# uNav4x4r1.net
KiCad netlist of a schematic drawn in EAGLE
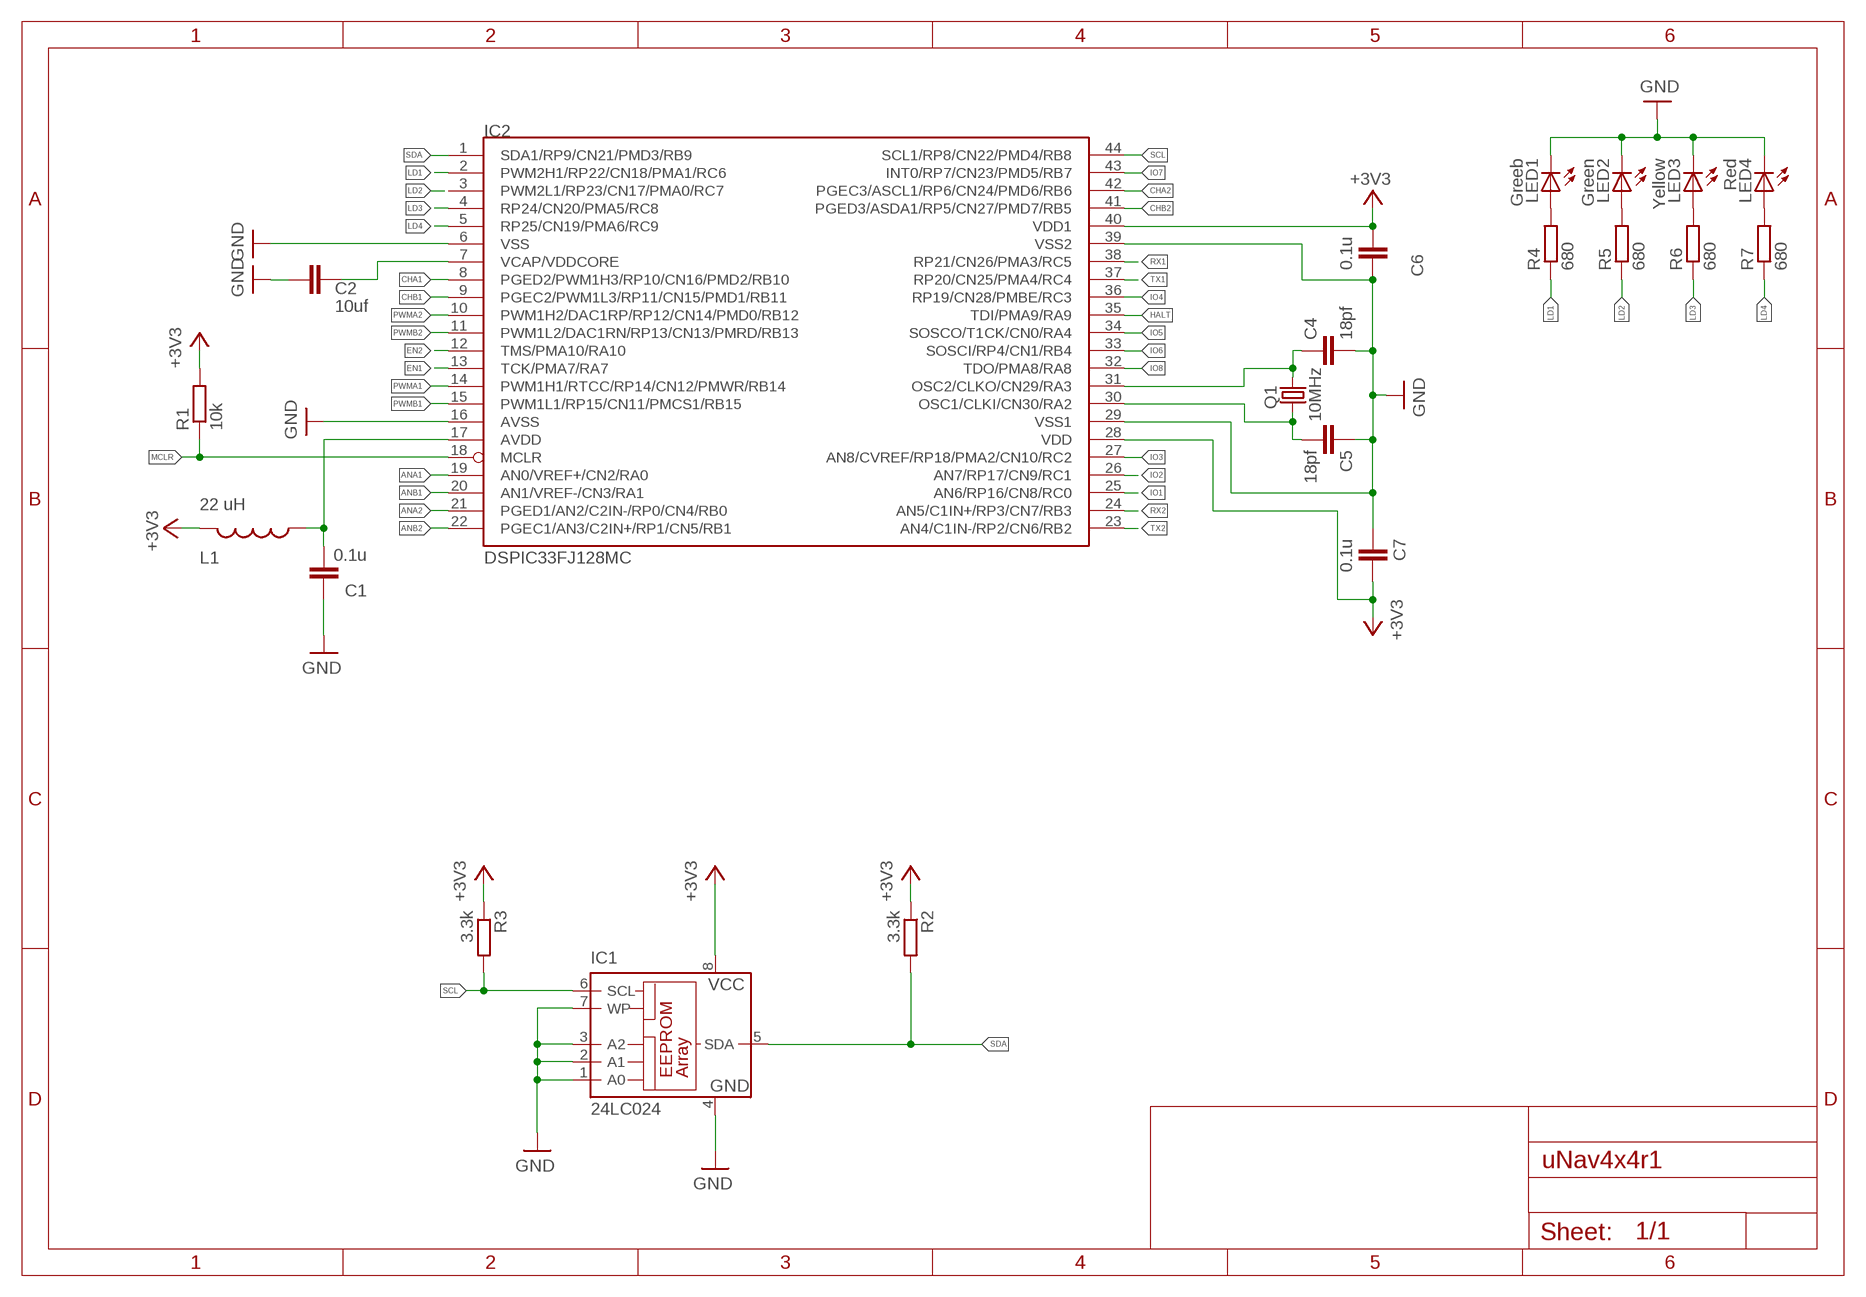
[diagram p0: schematic, sheet 1, part 1 of 2]
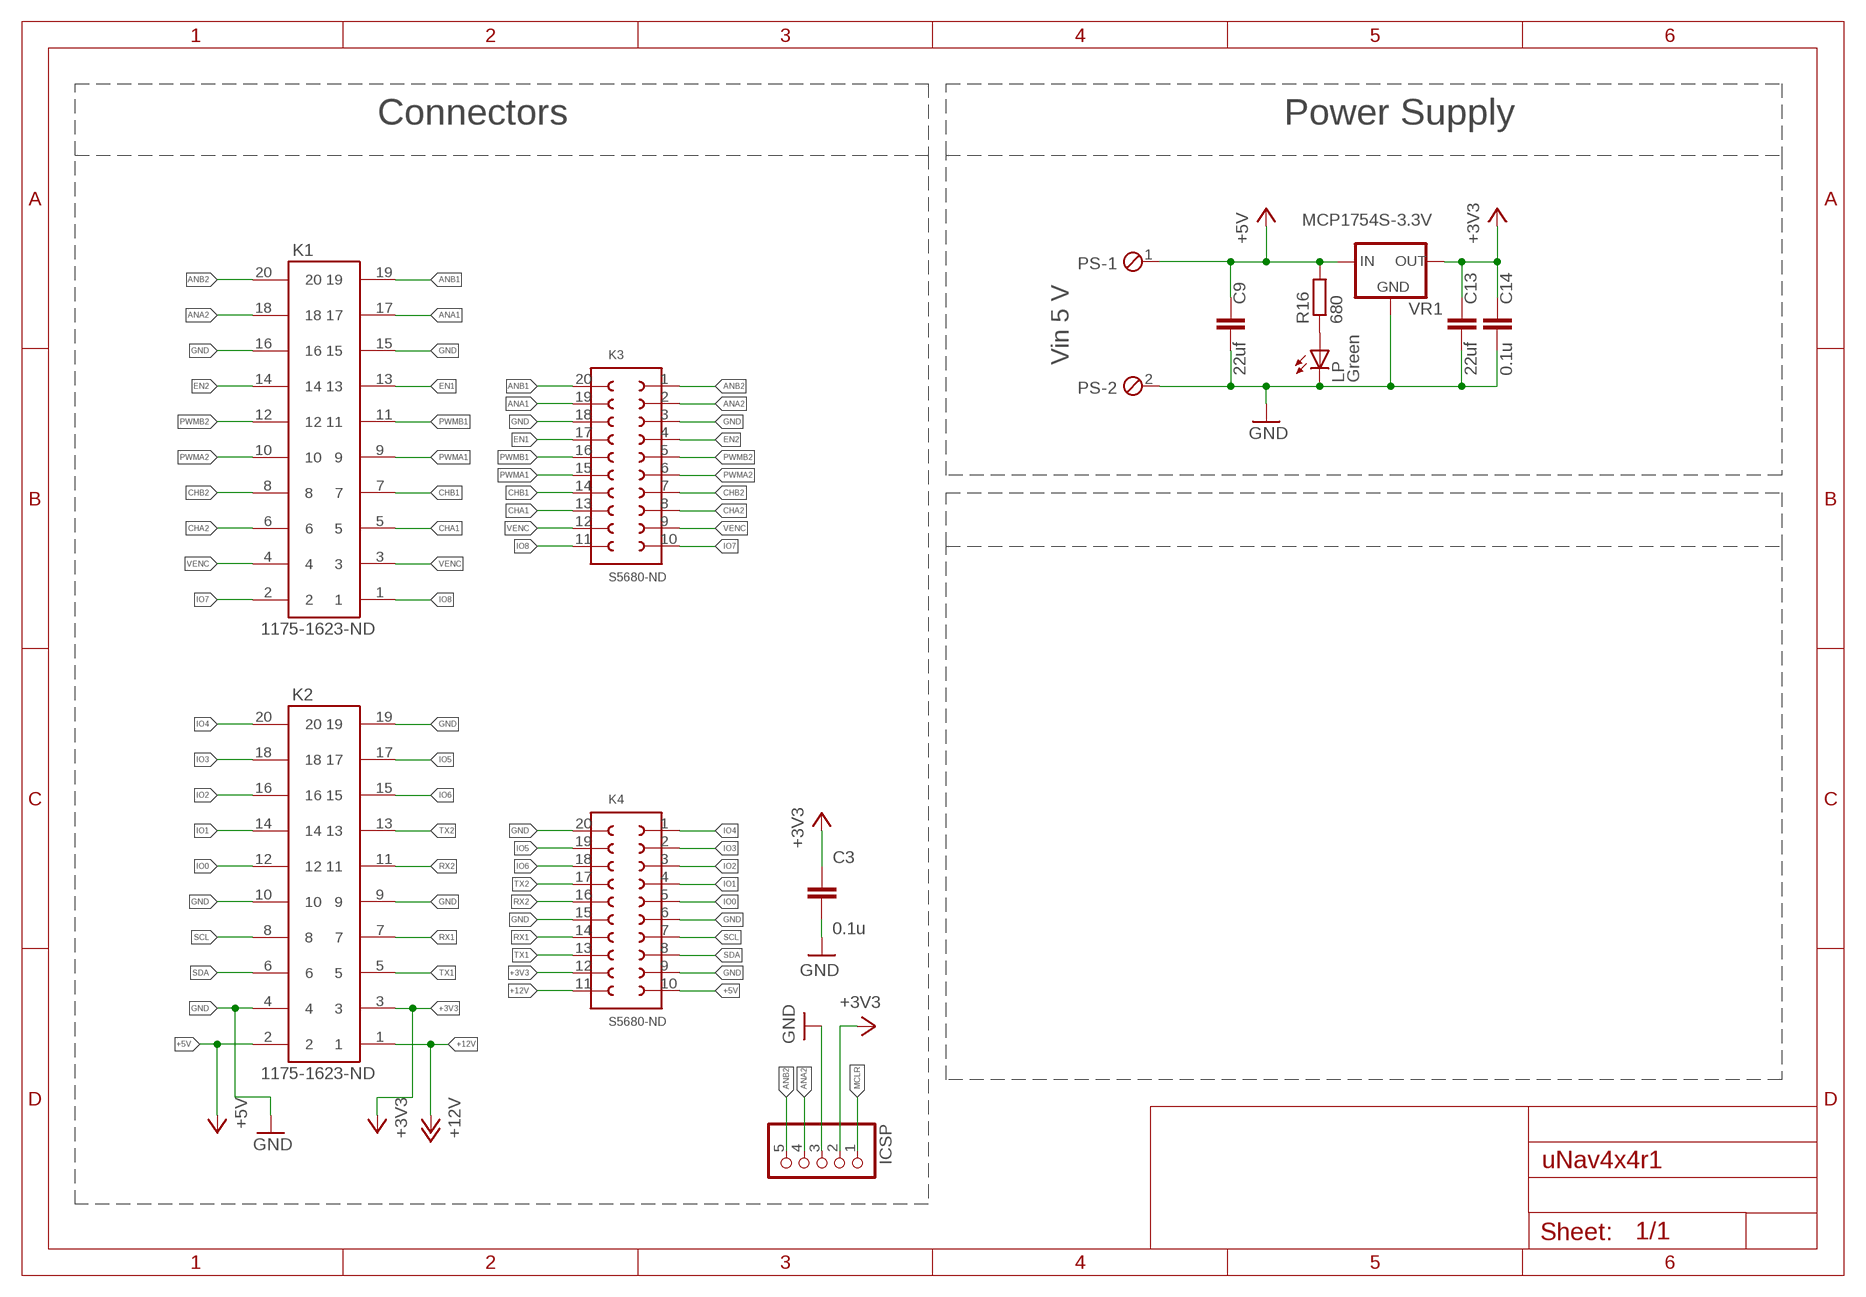
[diagram p1: schematic, sheet 1, part 2 of 2]

(export (version "E")
  (design (tool "Eeschema 10.0.6"))
  (components
    (comp (ref "C1")
      (value "0.1u")
      (footprint "eagle-import:C0603")
      (libsource (lib "eagle-import") (part "C-EUC0603"))
    )
    (comp (ref "C2")
      (value "10uf")
      (footprint "eagle-import:C1206")
      (libsource (lib "eagle-import") (part "C-EUC1206"))
    )
    (comp (ref "C3")
      (value "0.1u")
      (footprint "eagle-import:C0603")
      (libsource (lib "eagle-import") (part "C-EUC0603"))
    )
    (comp (ref "C4")
      (value "18pf")
      (footprint "eagle-import:C0603")
      (libsource (lib "eagle-import") (part "C-EUC0603"))
    )
    (comp (ref "C5")
      (value "18pf")
      (footprint "eagle-import:C0603")
      (libsource (lib "eagle-import") (part "C-EUC0603"))
    )
    (comp (ref "C6")
      (value "0.1u")
      (footprint "eagle-import:C0603")
      (libsource (lib "eagle-import") (part "C-EUC0603"))
    )
    (comp (ref "C7")
      (value "0.1u")
      (footprint "eagle-import:C0603")
      (libsource (lib "eagle-import") (part "C-EUC0603"))
    )
    (comp (ref "C9")
      (value "22uf")
      (footprint "eagle-import:C1206")
      (libsource (lib "eagle-import") (part "C-EUC1206"))
    )
    (comp (ref "C13")
      (value "22uf")
      (footprint "eagle-import:C1206")
      (libsource (lib "eagle-import") (part "C-EUC1206"))
    )
    (comp (ref "C14")
      (value "0.1u")
      (footprint "eagle-import:C0603")
      (libsource (lib "eagle-import") (part "C-EUC0603"))
    )
    (comp (ref "IC1")
      (value "24LC024")
      (footprint "eagle-import:SO-08M")
      (fields (field (name "MF") "MICROCHIP") (field (name "MPN") "24AA01-I/SN"))
      (libsource (lib "eagle-import") (part "24SMAA01"))
    )
    (comp (ref "IC2")
      (value "DSPIC33FJ128MC")
      (footprint "eagle-import:TQFP44")
      (libsource (lib "eagle-import") (part "DSPIC33FJ128MC804-PT"))
    )
    (comp (ref "ICSP")
      (value "PINHD-1X05_2.54-S")
      (footprint "eagle-import:1X05-S")
      (libsource (lib "eagle-import") (part "PINHD-1X05_2.54-S"))
    )
    (comp (ref "K1")
      (value "1175-1623-ND")
      (footprint "eagle-import:612X2020621")
      (libsource (lib "eagle-import") (part "612X2020621"))
    )
    (comp (ref "K2")
      (value "1175-1623-ND")
      (footprint "eagle-import:612X2020621")
      (libsource (lib "eagle-import") (part "612X2020621"))
    )
    (comp (ref "K3")
      (value "S5680-ND")
      (footprint "eagle-import:61002021821")
      (libsource (lib "eagle-import") (part "61002021821"))
    )
    (comp (ref "K4")
      (value "S5680-ND")
      (footprint "eagle-import:61002021821")
      (libsource (lib "eagle-import") (part "61002021821"))
    )
    (comp (ref "L1")
      (value "22 uH")
      (footprint "eagle-import:0805")
      (libsource (lib "eagle-import") (part "INDUCTOR0805"))
    )
    (comp (ref "LED1")
      (value "Greeb")
      (footprint "eagle-import:CHIPLED_0805")
      (libsource (lib "eagle-import") (part "LEDCHIPLED_0805"))
    )
    (comp (ref "LED2")
      (value "Green")
      (footprint "eagle-import:CHIPLED_0805")
      (libsource (lib "eagle-import") (part "LEDCHIPLED_0805"))
    )
    (comp (ref "LED3")
      (value "Yellow")
      (footprint "eagle-import:CHIPLED_0805")
      (libsource (lib "eagle-import") (part "LEDCHIPLED_0805"))
    )
    (comp (ref "LED4")
      (value "Red")
      (footprint "eagle-import:CHIPLED_0805")
      (libsource (lib "eagle-import") (part "LEDCHIPLED_0805"))
    )
    (comp (ref "LP")
      (value "Green")
      (footprint "eagle-import:CHIPLED_0805")
      (libsource (lib "eagle-import") (part "LEDCHIPLED_0805"))
    )
    (comp (ref "PS")
      (value "MPT2")
      (footprint "eagle-import:2POL254")
      (libsource (lib "eagle-import") (part "MPT2"))
    )
    (comp (ref "Q1")
      (value "10MHz")
      (footprint "eagle-import:HC49U-V")
      (libsource (lib "eagle-import") (part "CRYSTALHC49U-V"))
    )
    (comp (ref "R1")
      (value "10k")
      (footprint "eagle-import:R0603")
      (libsource (lib "eagle-import") (part "R-EU_R0603"))
    )
    (comp (ref "R2")
      (value "3.3k")
      (footprint "eagle-import:R0603")
      (libsource (lib "eagle-import") (part "R-EU_R0603"))
    )
    (comp (ref "R3")
      (value "3.3k")
      (footprint "eagle-import:R0603")
      (libsource (lib "eagle-import") (part "R-EU_R0603"))
    )
    (comp (ref "R4")
      (value "680")
      (footprint "eagle-import:R0603")
      (libsource (lib "eagle-import") (part "R-EU_R0603"))
    )
    (comp (ref "R5")
      (value "680")
      (footprint "eagle-import:R0603")
      (libsource (lib "eagle-import") (part "R-EU_R0603"))
    )
    (comp (ref "R6")
      (value "680")
      (footprint "eagle-import:R0603")
      (libsource (lib "eagle-import") (part "R-EU_R0603"))
    )
    (comp (ref "R7")
      (value "680")
      (footprint "eagle-import:R0603")
      (libsource (lib "eagle-import") (part "R-EU_R0603"))
    )
    (comp (ref "R16")
      (value "680")
      (footprint "eagle-import:R0603")
      (libsource (lib "eagle-import") (part "R-EU_R0603"))
    )
    (comp (ref "VR1")
      (value "MCP1754S-3.3V")
      (footprint "eagle-import:SOT89")
      (libsource (lib "eagle-import") (part "MCP1754S"))
    )
  )
  (nets
    (net (code "1") (name "+3V3") (class "Default")
      (node (ref "C13") (pin "1") (pinfunction "1_1") (pintype "passive"))
      (node (ref "C14") (pin "1") (pinfunction "1_1") (pintype "passive"))
      (node (ref "C3") (pin "1") (pinfunction "1_1") (pintype "passive"))
      (node (ref "C6") (pin "2") (pinfunction "2_2") (pintype "passive"))
      (node (ref "C7") (pin "1") (pinfunction "1_1") (pintype "passive"))
      (node (ref "IC1") (pin "8") (pinfunction "VCC_8") (pintype "power_in"))
      (node (ref "IC2") (pin "28") (pinfunction "VDD_28") (pintype "power_in"))
      (node (ref "IC2") (pin "40") (pinfunction "VDD1_40") (pintype "power_in"))
      (node (ref "ICSP") (pin "2") (pinfunction "2_2") (pintype "passive"))
      (node (ref "K2") (pin "3") (pinfunction "3_3") (pintype "passive"))
      (node (ref "K4") (pin "12") (pinfunction "12_12") (pintype "passive"))
      (node (ref "L1") (pin "2") (pinfunction "2_2") (pintype "passive"))
      (node (ref "R1") (pin "2") (pinfunction "2_2") (pintype "passive"))
      (node (ref "R2") (pin "1") (pinfunction "1_1") (pintype "passive"))
      (node (ref "R3") (pin "1") (pinfunction "1_1") (pintype "passive"))
      (node (ref "VR1") (pin "3") (pinfunction "OUT_3") (pintype "passive"))
    )
    (net (code "2") (name "+5V") (class "Default")
      (node (ref "C9") (pin "1") (pinfunction "1_1") (pintype "passive"))
      (node (ref "K2") (pin "2") (pinfunction "2_2") (pintype "passive"))
      (node (ref "K4") (pin "10") (pinfunction "10_10") (pintype "passive"))
      (node (ref "PS") (pin "1") (pinfunction "1_1") (pintype "passive"))
      (node (ref "R16") (pin "2") (pinfunction "2_2") (pintype "passive"))
      (node (ref "VR1") (pin "1") (pinfunction "IN_1") (pintype "input"))
    )
    (net (code "3") (name "+12V") (class "Default")
      (node (ref "K2") (pin "1") (pinfunction "1_1") (pintype "passive"))
      (node (ref "K4") (pin "11") (pinfunction "11_11") (pintype "passive"))
    )
    (net (code "4") (name "ANA1") (class "Default")
      (node (ref "IC2") (pin "19") (pinfunction "AN0/VREF+/CN2/RA0_19") (pintype "bidirectional"))
      (node (ref "K1") (pin "17") (pinfunction "17_17") (pintype "passive"))
      (node (ref "K3") (pin "19") (pinfunction "19_19") (pintype "passive"))
    )
    (net (code "5") (name "ANA2") (class "Default")
      (node (ref "IC2") (pin "21") (pinfunction "PGED1/AN2/C2IN-/RP0/CN4/RB0_21") (pintype "bidirectional"))
      (node (ref "ICSP") (pin "4") (pinfunction "4_4") (pintype "passive"))
      (node (ref "K1") (pin "18") (pinfunction "18_18") (pintype "passive"))
      (node (ref "K3") (pin "2") (pinfunction "2_2") (pintype "passive"))
    )
    (net (code "6") (name "ANB1") (class "Default")
      (node (ref "IC2") (pin "20") (pinfunction "AN1/VREF-/CN3/RA1_20") (pintype "bidirectional"))
      (node (ref "K1") (pin "19") (pinfunction "19_19") (pintype "passive"))
      (node (ref "K3") (pin "20") (pinfunction "20_20") (pintype "passive"))
    )
    (net (code "7") (name "ANB2") (class "Default")
      (node (ref "IC2") (pin "22") (pinfunction "PGEC1/AN3/C2IN+/RP1/CN5/RB1_22") (pintype "bidirectional"))
      (node (ref "ICSP") (pin "5") (pinfunction "5_5") (pintype "passive"))
      (node (ref "K1") (pin "20") (pinfunction "20_20") (pintype "passive"))
      (node (ref "K3") (pin "1") (pinfunction "1_1") (pintype "passive"))
    )
    (net (code "8") (name "CHA1") (class "Default")
      (node (ref "IC2") (pin "8") (pinfunction "PGED2/PWM1H3/RP10/CN16/PMD2/RB10_8") (pintype "bidirectional"))
      (node (ref "K1") (pin "5") (pinfunction "5_5") (pintype "passive"))
      (node (ref "K3") (pin "13") (pinfunction "13_13") (pintype "passive"))
    )
    (net (code "9") (name "CHA2") (class "Default")
      (node (ref "IC2") (pin "42") (pinfunction "PGEC3/ASCL1/RP6/CN24/PMD6/RB6_42") (pintype "bidirectional"))
      (node (ref "K1") (pin "6") (pinfunction "6_6") (pintype "passive"))
      (node (ref "K3") (pin "8") (pinfunction "8_8") (pintype "passive"))
    )
    (net (code "10") (name "CHB1") (class "Default")
      (node (ref "IC2") (pin "9") (pinfunction "PGEC2/PWM1L3/RP11/CN15/PMD1/RB11_9") (pintype "bidirectional"))
      (node (ref "K1") (pin "7") (pinfunction "7_7") (pintype "passive"))
      (node (ref "K3") (pin "14") (pinfunction "14_14") (pintype "passive"))
    )
    (net (code "11") (name "CHB2") (class "Default")
      (node (ref "IC2") (pin "41") (pinfunction "PGED3/ASDA1/RP5/CN27/PMD7/RB5_41") (pintype "bidirectional"))
      (node (ref "K1") (pin "8") (pinfunction "8_8") (pintype "passive"))
      (node (ref "K3") (pin "7") (pinfunction "7_7") (pintype "passive"))
    )
    (net (code "12") (name "EN1") (class "Default")
      (node (ref "IC2") (pin "13") (pinfunction "TCK/PMA7/RA7_13") (pintype "bidirectional"))
      (node (ref "K1") (pin "13") (pinfunction "13_13") (pintype "passive"))
      (node (ref "K3") (pin "17") (pinfunction "17_17") (pintype "passive"))
    )
    (net (code "13") (name "EN2") (class "Default")
      (node (ref "IC2") (pin "12") (pinfunction "TMS/PMA10/RA10_12") (pintype "bidirectional"))
      (node (ref "K1") (pin "14") (pinfunction "14_14") (pintype "passive"))
      (node (ref "K3") (pin "4") (pinfunction "4_4") (pintype "passive"))
    )
    (net (code "14") (name "GND") (class "Default")
      (node (ref "C1") (pin "1") (pinfunction "1_1") (pintype "passive"))
      (node (ref "C13") (pin "2") (pinfunction "2_2") (pintype "passive"))
      (node (ref "C14") (pin "2") (pinfunction "2_2") (pintype "passive"))
      (node (ref "C2") (pin "2") (pinfunction "2_2") (pintype "passive"))
      (node (ref "C3") (pin "2") (pinfunction "2_2") (pintype "passive"))
      (node (ref "C4") (pin "2") (pinfunction "2_2") (pintype "passive"))
      (node (ref "C5") (pin "1") (pinfunction "1_1") (pintype "passive"))
      (node (ref "C6") (pin "1") (pinfunction "1_1") (pintype "passive"))
      (node (ref "C7") (pin "2") (pinfunction "2_2") (pintype "passive"))
      (node (ref "C9") (pin "2") (pinfunction "2_2") (pintype "passive"))
      (node (ref "IC1") (pin "1") (pinfunction "A0_1") (pintype "input"))
      (node (ref "IC1") (pin "2") (pinfunction "A1_2") (pintype "input"))
      (node (ref "IC1") (pin "3") (pinfunction "A2_3") (pintype "input"))
      (node (ref "IC1") (pin "4") (pinfunction "GND_4") (pintype "power_in"))
      (node (ref "IC1") (pin "7") (pinfunction "WP_7") (pintype "input"))
      (node (ref "IC2") (pin "16") (pinfunction "AVSS_16") (pintype "power_in"))
      (node (ref "IC2") (pin "29") (pinfunction "VSS1_29") (pintype "power_in"))
      (node (ref "IC2") (pin "39") (pinfunction "VSS2_39") (pintype "power_in"))
      (node (ref "IC2") (pin "6") (pinfunction "VSS_6") (pintype "power_in"))
      (node (ref "ICSP") (pin "3") (pinfunction "3_3") (pintype "passive"))
      (node (ref "K1") (pin "15") (pinfunction "15_15") (pintype "passive"))
      (node (ref "K1") (pin "16") (pinfunction "16_16") (pintype "passive"))
      (node (ref "K2") (pin "10") (pinfunction "10_10") (pintype "passive"))
      (node (ref "K2") (pin "19") (pinfunction "19_19") (pintype "passive"))
      (node (ref "K2") (pin "4") (pinfunction "4_4") (pintype "passive"))
      (node (ref "K2") (pin "9") (pinfunction "9_9") (pintype "passive"))
      (node (ref "K3") (pin "18") (pinfunction "18_18") (pintype "passive"))
      (node (ref "K3") (pin "3") (pinfunction "3_3") (pintype "passive"))
      (node (ref "K4") (pin "15") (pinfunction "15_15") (pintype "passive"))
      (node (ref "K4") (pin "20") (pinfunction "20_20") (pintype "passive"))
      (node (ref "K4") (pin "6") (pinfunction "6_6") (pintype "passive"))
      (node (ref "K4") (pin "9") (pinfunction "9_9") (pintype "passive"))
      (node (ref "LED1") (pin "C") (pinfunction "C_C") (pintype "passive"))
      (node (ref "LED2") (pin "C") (pinfunction "C_C") (pintype "passive"))
      (node (ref "LED3") (pin "C") (pinfunction "C_C") (pintype "passive"))
      (node (ref "LED4") (pin "C") (pinfunction "C_C") (pintype "passive"))
      (node (ref "LP") (pin "C") (pinfunction "C_C") (pintype "passive"))
      (node (ref "PS") (pin "2") (pinfunction "1_2") (pintype "passive"))
      (node (ref "VR1") (pin "2") (pinfunction "GND_2") (pintype "input"))
      (node (ref "VR1") (pin "4") (pinfunction "GND_4") (pintype "input"))
    )
    (net (code "15") (name "HALT") (class "Default")
      (node (ref "IC2") (pin "35") (pinfunction "TDI/PMA9/RA9_35") (pintype "bidirectional"))
    )
    (net (code "16") (name "IO0") (class "Default")
      (node (ref "K2") (pin "12") (pinfunction "12_12") (pintype "passive"))
      (node (ref "K4") (pin "5") (pinfunction "5_5") (pintype "passive"))
    )
    (net (code "17") (name "IO1") (class "Default")
      (node (ref "IC2") (pin "25") (pinfunction "AN6/RP16/CN8/RC0_25") (pintype "bidirectional"))
      (node (ref "K2") (pin "14") (pinfunction "14_14") (pintype "passive"))
      (node (ref "K4") (pin "4") (pinfunction "4_4") (pintype "passive"))
    )
    (net (code "18") (name "IO2") (class "Default")
      (node (ref "IC2") (pin "26") (pinfunction "AN7/RP17/CN9/RC1_26") (pintype "bidirectional"))
      (node (ref "K2") (pin "16") (pinfunction "16_16") (pintype "passive"))
      (node (ref "K4") (pin "3") (pinfunction "3_3") (pintype "passive"))
    )
    (net (code "19") (name "IO3") (class "Default")
      (node (ref "IC2") (pin "27") (pinfunction "AN8/CVREF/RP18/PMA2/CN10/RC2_27") (pintype "bidirectional"))
      (node (ref "K2") (pin "18") (pinfunction "18_18") (pintype "passive"))
      (node (ref "K4") (pin "2") (pinfunction "2_2") (pintype "passive"))
    )
    (net (code "20") (name "IO4") (class "Default")
      (node (ref "IC2") (pin "36") (pinfunction "RP19/CN28/PMBE/RC3_36") (pintype "bidirectional"))
      (node (ref "K2") (pin "20") (pinfunction "20_20") (pintype "passive"))
      (node (ref "K4") (pin "1") (pinfunction "1_1") (pintype "passive"))
    )
    (net (code "21") (name "IO5") (class "Default")
      (node (ref "IC2") (pin "34") (pinfunction "SOSCO/T1CK/CN0/RA4_34") (pintype "bidirectional"))
      (node (ref "K2") (pin "17") (pinfunction "17_17") (pintype "passive"))
      (node (ref "K4") (pin "19") (pinfunction "19_19") (pintype "passive"))
    )
    (net (code "22") (name "IO6") (class "Default")
      (node (ref "IC2") (pin "33") (pinfunction "SOSCI/RP4/CN1/RB4_33") (pintype "bidirectional"))
      (node (ref "K2") (pin "15") (pinfunction "15_15") (pintype "passive"))
      (node (ref "K4") (pin "18") (pinfunction "18_18") (pintype "passive"))
    )
    (net (code "23") (name "IO7") (class "Default")
      (node (ref "IC2") (pin "43") (pinfunction "INT0/RP7/CN23/PMD5/RB7_43") (pintype "bidirectional"))
      (node (ref "K1") (pin "2") (pinfunction "2_2") (pintype "passive"))
      (node (ref "K3") (pin "10") (pinfunction "10_10") (pintype "passive"))
    )
    (net (code "24") (name "IO8") (class "Default")
      (node (ref "IC2") (pin "32") (pinfunction "TDO/PMA8/RA8_32") (pintype "bidirectional"))
      (node (ref "K1") (pin "1") (pinfunction "1_1") (pintype "passive"))
      (node (ref "K3") (pin "11") (pinfunction "11_11") (pintype "passive"))
    )
    (net (code "25") (name "LD1") (class "Default")
      (node (ref "IC2") (pin "2") (pinfunction "PWM2H1/RP22/CN18/PMA1/RC6_2") (pintype "bidirectional"))
      (node (ref "R4") (pin "1") (pinfunction "1_1") (pintype "passive"))
    )
    (net (code "26") (name "LD2") (class "Default")
      (node (ref "IC2") (pin "3") (pinfunction "PWM2L1/RP23/CN17/PMA0/RC7_3") (pintype "bidirectional"))
      (node (ref "R5") (pin "1") (pinfunction "1_1") (pintype "passive"))
    )
    (net (code "27") (name "LD3") (class "Default")
      (node (ref "IC2") (pin "4") (pinfunction "RP24/CN20/PMA5/RC8_4") (pintype "bidirectional"))
      (node (ref "R6") (pin "1") (pinfunction "1_1") (pintype "passive"))
    )
    (net (code "28") (name "LD4") (class "Default")
      (node (ref "IC2") (pin "5") (pinfunction "RP25/CN19/PMA6/RC9_5") (pintype "bidirectional"))
      (node (ref "R7") (pin "1") (pinfunction "1_1") (pintype "passive"))
    )
    (net (code "29") (name "MCLR") (class "Default")
      (node (ref "IC2") (pin "18") (pinfunction "MCLR_18") (pintype "input"))
      (node (ref "ICSP") (pin "1") (pinfunction "1_1") (pintype "passive"))
      (node (ref "R1") (pin "1") (pinfunction "1_1") (pintype "passive"))
    )
    (net (code "30") (name "Net-(IC2-AVDD)") (class "Default")
      (node (ref "C1") (pin "2") (pinfunction "2_2") (pintype "passive"))
      (node (ref "IC2") (pin "17") (pinfunction "AVDD_17") (pintype "power_in"))
      (node (ref "L1") (pin "1") (pinfunction "1_1") (pintype "passive"))
    )
    (net (code "31") (name "Net-(IC2-OSC1{slash}CLKI{slash}CN30{slash}RA2)") (class "Default")
      (node (ref "C5") (pin "2") (pinfunction "2_2") (pintype "passive"))
      (node (ref "IC2") (pin "30") (pinfunction "OSC1/CLKI/CN30/RA2_30") (pintype "bidirectional"))
      (node (ref "Q1") (pin "1") (pinfunction "1_1") (pintype "passive"))
    )
    (net (code "32") (name "Net-(IC2-OSC2{slash}CLKO{slash}CN29{slash}RA3)") (class "Default")
      (node (ref "C4") (pin "1") (pinfunction "1_1") (pintype "passive"))
      (node (ref "IC2") (pin "31") (pinfunction "OSC2/CLKO/CN29/RA3_31") (pintype "bidirectional"))
      (node (ref "Q1") (pin "2") (pinfunction "2_2") (pintype "passive"))
    )
    (net (code "33") (name "Net-(IC2-VCAP{slash}VDDCORE)") (class "Default")
      (node (ref "C2") (pin "1") (pinfunction "1_1") (pintype "passive"))
      (node (ref "IC2") (pin "7") (pinfunction "VCAP/VDDCORE_7") (pintype "power_in"))
    )
    (net (code "34") (name "Net-(LED1-PadA)") (class "Default")
      (node (ref "LED1") (pin "A") (pinfunction "A_A") (pintype "passive"))
      (node (ref "R4") (pin "2") (pinfunction "2_2") (pintype "passive"))
    )
    (net (code "35") (name "Net-(LED2-PadA)") (class "Default")
      (node (ref "LED2") (pin "A") (pinfunction "A_A") (pintype "passive"))
      (node (ref "R5") (pin "2") (pinfunction "2_2") (pintype "passive"))
    )
    (net (code "36") (name "Net-(LED3-PadA)") (class "Default")
      (node (ref "LED3") (pin "A") (pinfunction "A_A") (pintype "passive"))
      (node (ref "R6") (pin "2") (pinfunction "2_2") (pintype "passive"))
    )
    (net (code "37") (name "Net-(LED4-PadA)") (class "Default")
      (node (ref "LED4") (pin "A") (pinfunction "A_A") (pintype "passive"))
      (node (ref "R7") (pin "2") (pinfunction "2_2") (pintype "passive"))
    )
    (net (code "38") (name "Net-(LP-PadA)") (class "Default")
      (node (ref "LP") (pin "A") (pinfunction "A_A") (pintype "passive"))
      (node (ref "R16") (pin "1") (pinfunction "1_1") (pintype "passive"))
    )
    (net (code "39") (name "PWMA1") (class "Default")
      (node (ref "IC2") (pin "14") (pinfunction "PWM1H1/RTCC/RP14/CN12/PMWR/RB14_14") (pintype "bidirectional"))
      (node (ref "K1") (pin "9") (pinfunction "9_9") (pintype "passive"))
      (node (ref "K3") (pin "15") (pinfunction "15_15") (pintype "passive"))
    )
    (net (code "40") (name "PWMA2") (class "Default")
      (node (ref "IC2") (pin "10") (pinfunction "PWM1H2/DAC1RP/RP12/CN14/PMD0/RB12_10") (pintype "bidirectional"))
      (node (ref "K1") (pin "10") (pinfunction "10_10") (pintype "passive"))
      (node (ref "K3") (pin "6") (pinfunction "6_6") (pintype "passive"))
    )
    (net (code "41") (name "PWMB1") (class "Default")
      (node (ref "IC2") (pin "15") (pinfunction "PWM1L1/RP15/CN11/PMCS1/RB15_15") (pintype "bidirectional"))
      (node (ref "K1") (pin "11") (pinfunction "11_11") (pintype "passive"))
      (node (ref "K3") (pin "16") (pinfunction "16_16") (pintype "passive"))
    )
    (net (code "42") (name "PWMB2") (class "Default")
      (node (ref "IC2") (pin "11") (pinfunction "PWM1L2/DAC1RN/RP13/CN13/PMRD/RB13_11") (pintype "bidirectional"))
      (node (ref "K1") (pin "12") (pinfunction "12_12") (pintype "passive"))
      (node (ref "K3") (pin "5") (pinfunction "5_5") (pintype "passive"))
    )
    (net (code "43") (name "RX1") (class "Default")
      (node (ref "IC2") (pin "38") (pinfunction "RP21/CN26/PMA3/RC5_38") (pintype "bidirectional"))
      (node (ref "K2") (pin "7") (pinfunction "7_7") (pintype "passive"))
      (node (ref "K4") (pin "14") (pinfunction "14_14") (pintype "passive"))
    )
    (net (code "44") (name "RX2") (class "Default")
      (node (ref "IC2") (pin "24") (pinfunction "AN5/C1IN+/RP3/CN7/RB3_24") (pintype "bidirectional"))
      (node (ref "K2") (pin "11") (pinfunction "11_11") (pintype "passive"))
      (node (ref "K4") (pin "16") (pinfunction "16_16") (pintype "passive"))
    )
    (net (code "45") (name "SCL") (class "Default")
      (node (ref "IC1") (pin "6") (pinfunction "SCL_6") (pintype "input"))
      (node (ref "IC2") (pin "44") (pinfunction "SCL1/RP8/CN22/PMD4/RB8_44") (pintype "bidirectional"))
      (node (ref "K2") (pin "8") (pinfunction "8_8") (pintype "passive"))
      (node (ref "K4") (pin "7") (pinfunction "7_7") (pintype "passive"))
      (node (ref "R3") (pin "2") (pinfunction "2_2") (pintype "passive"))
    )
    (net (code "46") (name "SDA") (class "Default")
      (node (ref "IC1") (pin "5") (pinfunction "SDA_5") (pintype "bidirectional"))
      (node (ref "IC2") (pin "1") (pinfunction "SDA1/RP9/CN21/PMD3/RB9_1") (pintype "bidirectional"))
      (node (ref "K2") (pin "6") (pinfunction "6_6") (pintype "passive"))
      (node (ref "K4") (pin "8") (pinfunction "8_8") (pintype "passive"))
      (node (ref "R2") (pin "2") (pinfunction "2_2") (pintype "passive"))
    )
    (net (code "47") (name "TX1") (class "Default")
      (node (ref "IC2") (pin "37") (pinfunction "RP20/CN25/PMA4/RC4_37") (pintype "bidirectional"))
      (node (ref "K2") (pin "5") (pinfunction "5_5") (pintype "passive"))
      (node (ref "K4") (pin "13") (pinfunction "13_13") (pintype "passive"))
    )
    (net (code "48") (name "TX2") (class "Default")
      (node (ref "IC2") (pin "23") (pinfunction "AN4/C1IN-/RP2/CN6/RB2_23") (pintype "bidirectional"))
      (node (ref "K2") (pin "13") (pinfunction "13_13") (pintype "passive"))
      (node (ref "K4") (pin "17") (pinfunction "17_17") (pintype "passive"))
    )
    (net (code "49") (name "VENC") (class "Default")
      (node (ref "K1") (pin "3") (pinfunction "3_3") (pintype "passive"))
      (node (ref "K1") (pin "4") (pinfunction "4_4") (pintype "passive"))
      (node (ref "K3") (pin "12") (pinfunction "12_12") (pintype "passive"))
      (node (ref "K3") (pin "9") (pinfunction "9_9") (pintype "passive"))
    )
  )
)
